# 07_LMS7002M_Power.net
KiCad netlist of a schematic drawn in Altium Designer
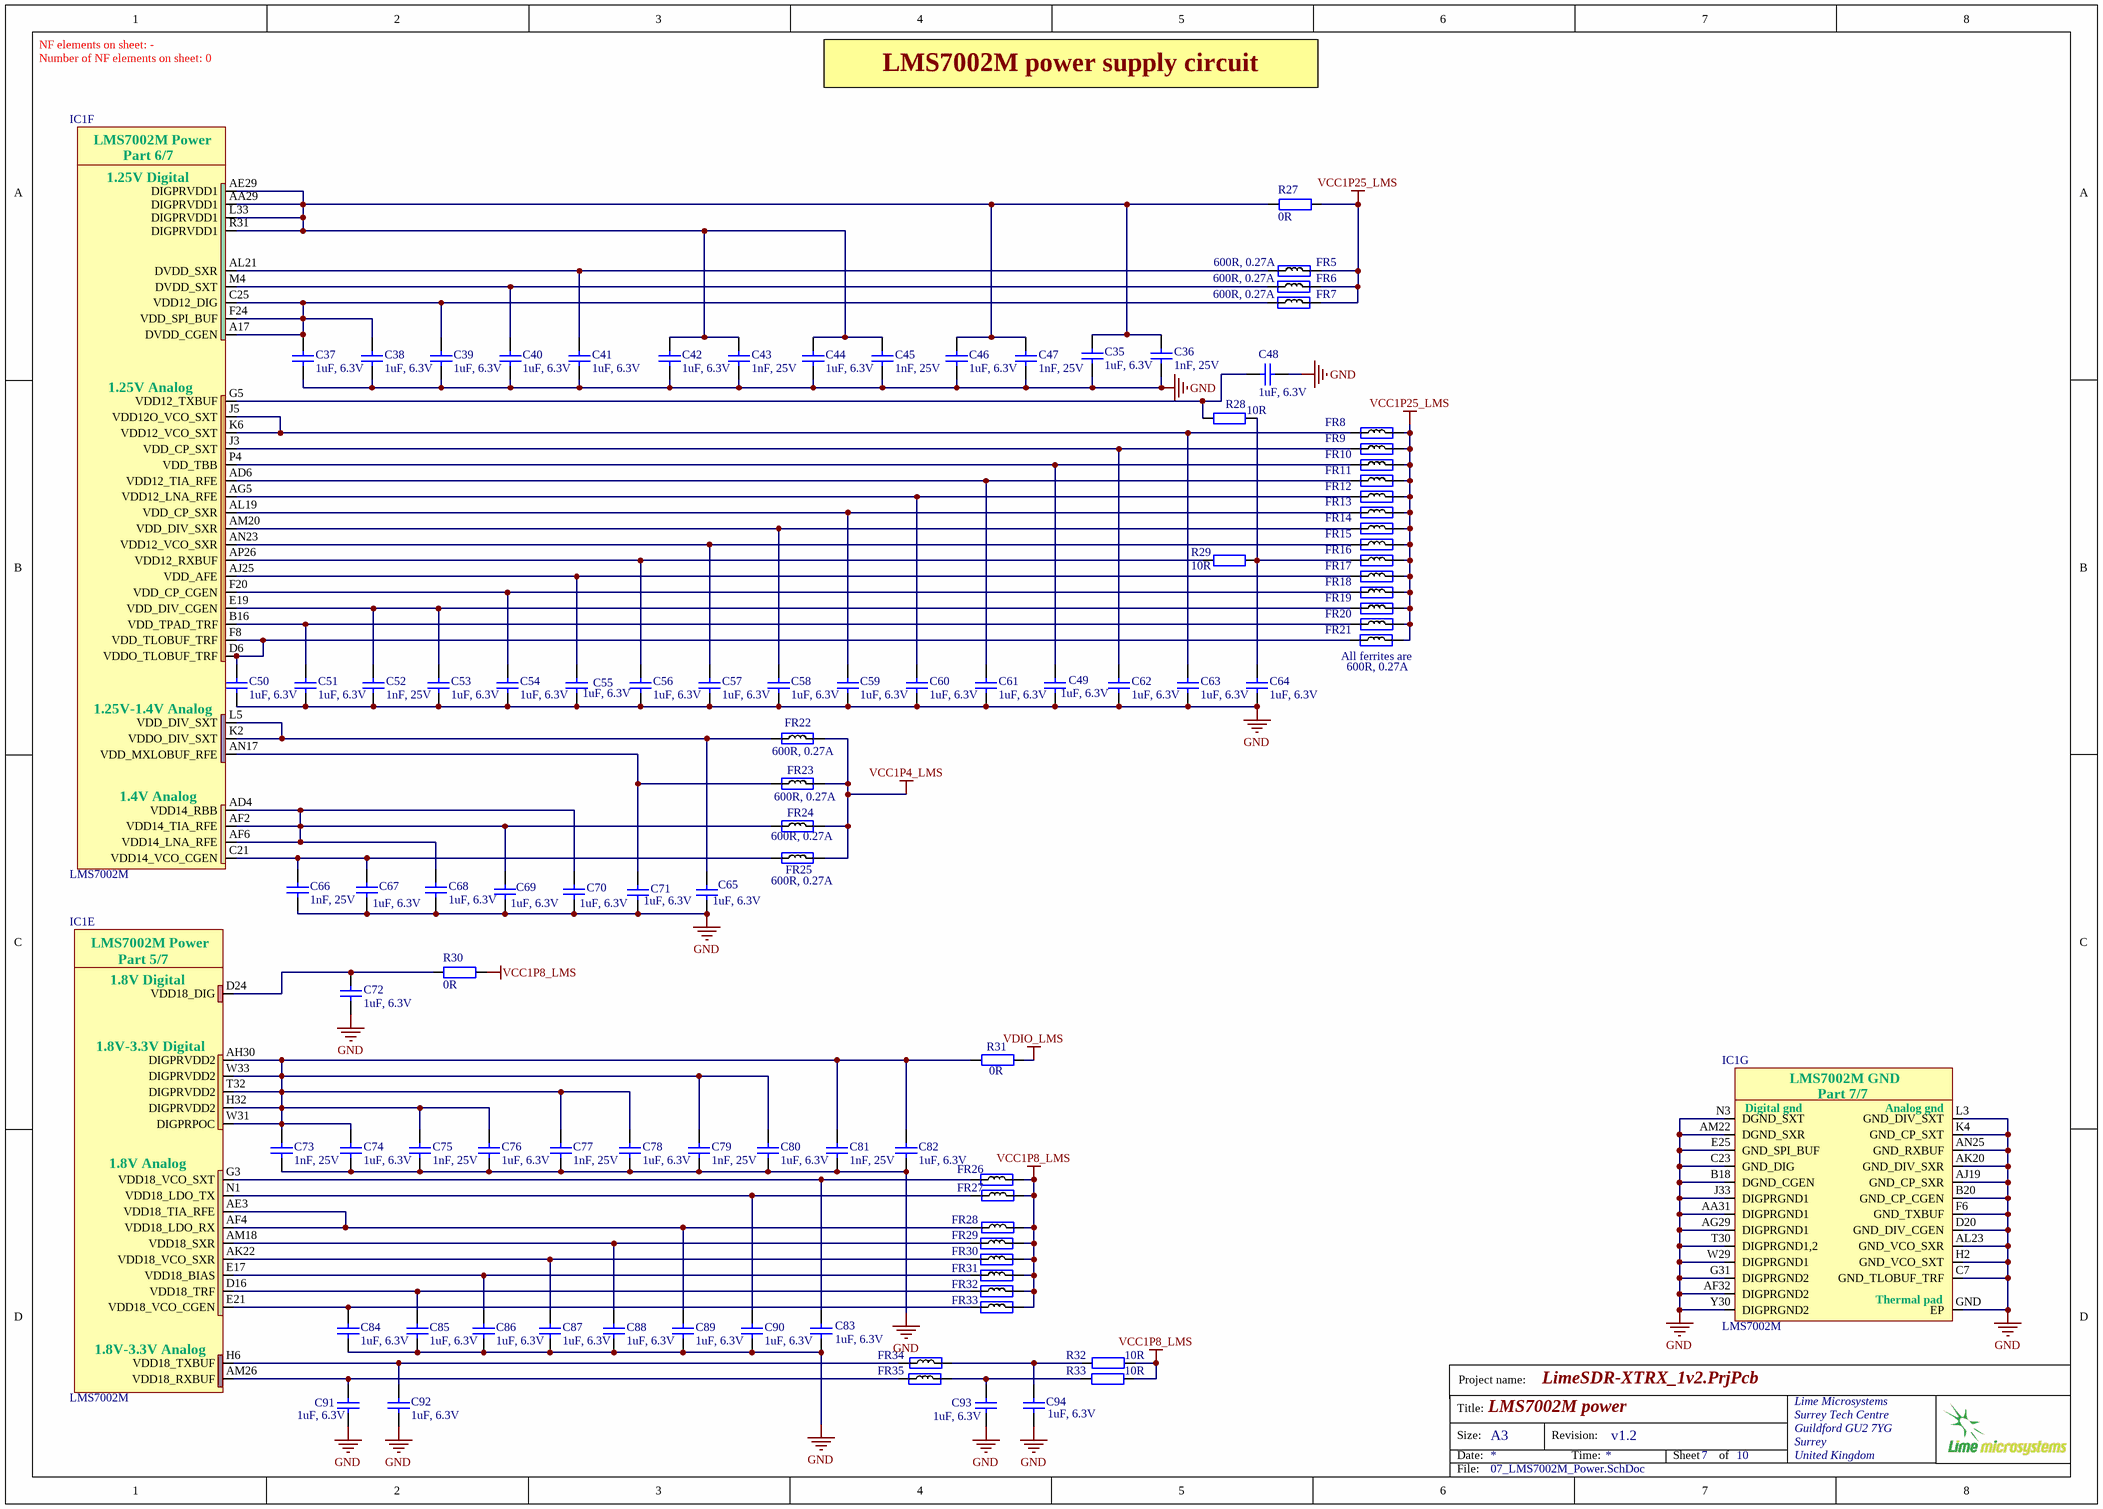
[diagram p0: 07_LMS7002M_Power.SchDoc]

(export (version "E")
  (design (tool "Eeschema 10.0.6"))
  (components
    (comp (ref "C35")
      (value "1uF, 6.3V")
      (footprint "CAP0201")
      (fields (field (name "TOLERANCE") "±20%") (field (name "MANUFACTURER") "TDK Corporation"))
      (libsource (lib "LimeMicroAltiumLib_schLib") (part "Cap_0402"))
    )
    (comp (ref "C36")
      (value "1nF, 25V")
      (footprint "CAP0201")
      (fields (field (name "TOLERANCE") "±10%") (field (name "MANUFACTURER") "TDK Corporation"))
      (libsource (lib "LimeMicroAltiumLib_schLib") (part "Cap_0402"))
    )
    (comp (ref "C37")
      (value "1uF, 6.3V")
      (footprint "CAP0201")
      (fields (field (name "TOLERANCE") "±20%") (field (name "MANUFACTURER") "TDK Corporation"))
      (libsource (lib "LimeMicroAltiumLib_schLib") (part "Cap_0402"))
    )
    (comp (ref "C38")
      (value "1uF, 6.3V")
      (footprint "CAP0201")
      (fields (field (name "TOLERANCE") "±20%") (field (name "MANUFACTURER") "TDK Corporation"))
      (libsource (lib "LimeMicroAltiumLib_schLib") (part "Cap_0402"))
    )
    (comp (ref "C39")
      (value "1uF, 6.3V")
      (footprint "CAP0201")
      (fields (field (name "TOLERANCE") "±20%") (field (name "MANUFACTURER") "TDK Corporation"))
      (libsource (lib "LimeMicroAltiumLib_schLib") (part "Cap_0402"))
    )
    (comp (ref "C40")
      (value "1uF, 6.3V")
      (footprint "CAP0201")
      (fields (field (name "TOLERANCE") "±20%") (field (name "MANUFACTURER") "TDK Corporation"))
      (libsource (lib "LimeMicroAltiumLib_schLib") (part "Cap_0402"))
    )
    (comp (ref "C41")
      (value "1uF, 6.3V")
      (footprint "CAP0201")
      (fields (field (name "TOLERANCE") "±20%") (field (name "MANUFACTURER") "TDK Corporation"))
      (libsource (lib "LimeMicroAltiumLib_schLib") (part "Cap_0402"))
    )
    (comp (ref "C42")
      (value "1uF, 6.3V")
      (footprint "CAP0201")
      (fields (field (name "TOLERANCE") "±20%") (field (name "MANUFACTURER") "TDK Corporation"))
      (libsource (lib "LimeMicroAltiumLib_schLib") (part "Cap_0402"))
    )
    (comp (ref "C43")
      (value "1nF, 25V")
      (footprint "CAP0201")
      (fields (field (name "TOLERANCE") "±10%") (field (name "MANUFACTURER") "TDK Corporation"))
      (libsource (lib "LimeMicroAltiumLib_schLib") (part "Cap_0402"))
    )
    (comp (ref "C44")
      (value "1uF, 6.3V")
      (footprint "CAP0201")
      (fields (field (name "TOLERANCE") "±20%") (field (name "MANUFACTURER") "TDK Corporation"))
      (libsource (lib "LimeMicroAltiumLib_schLib") (part "Cap_0402"))
    )
    (comp (ref "C45")
      (value "1nF, 25V")
      (footprint "CAP0201")
      (fields (field (name "TOLERANCE") "±10%") (field (name "MANUFACTURER") "TDK Corporation"))
      (libsource (lib "LimeMicroAltiumLib_schLib") (part "Cap_0402"))
    )
    (comp (ref "C46")
      (value "1uF, 6.3V")
      (footprint "CAP0201")
      (fields (field (name "TOLERANCE") "±20%") (field (name "MANUFACTURER") "TDK Corporation"))
      (libsource (lib "LimeMicroAltiumLib_schLib") (part "Cap_0402"))
    )
    (comp (ref "C47")
      (value "1nF, 25V")
      (footprint "CAP0201")
      (fields (field (name "TOLERANCE") "±10%") (field (name "MANUFACTURER") "TDK Corporation"))
      (libsource (lib "LimeMicroAltiumLib_schLib") (part "Cap_0402"))
    )
    (comp (ref "C48")
      (value "1uF, 6.3V")
      (footprint "CAP0201")
      (fields (field (name "TOLERANCE") "±20%") (field (name "MANUFACTURER") "TDK Corporation"))
      (libsource (lib "LimeMicroAltiumLib_schLib") (part "Cap_0402"))
    )
    (comp (ref "C49")
      (value "1uF, 6.3V")
      (footprint "CAP0201")
      (fields (field (name "TOLERANCE") "±20%") (field (name "MANUFACTURER") "TDK Corporation"))
      (libsource (lib "LimeMicroAltiumLib_schLib") (part "Cap_0402"))
    )
    (comp (ref "C50")
      (value "1uF, 6.3V")
      (footprint "CAP0201")
      (fields (field (name "TOLERANCE") "±20%") (field (name "MANUFACTURER") "TDK Corporation"))
      (libsource (lib "LimeMicroAltiumLib_schLib") (part "Cap_0402"))
    )
    (comp (ref "C51")
      (value "1uF, 6.3V")
      (footprint "CAP0201")
      (fields (field (name "TOLERANCE") "±20%") (field (name "MANUFACTURER") "TDK Corporation"))
      (libsource (lib "LimeMicroAltiumLib_schLib") (part "Cap_0402"))
    )
    (comp (ref "C52")
      (value "1nF, 25V")
      (footprint "CAP0201")
      (fields (field (name "TOLERANCE") "±10%") (field (name "MANUFACTURER") "TDK Corporation"))
      (libsource (lib "LimeMicroAltiumLib_schLib") (part "Cap_0402"))
    )
    (comp (ref "C53")
      (value "1uF, 6.3V")
      (footprint "CAP0201")
      (fields (field (name "TOLERANCE") "±20%") (field (name "MANUFACTURER") "TDK Corporation"))
      (libsource (lib "LimeMicroAltiumLib_schLib") (part "Cap_0402"))
    )
    (comp (ref "C54")
      (value "1uF, 6.3V")
      (footprint "CAP0201")
      (fields (field (name "TOLERANCE") "±20%") (field (name "MANUFACTURER") "TDK Corporation"))
      (libsource (lib "LimeMicroAltiumLib_schLib") (part "Cap_0402"))
    )
    (comp (ref "C55")
      (value "1uF, 6.3V")
      (footprint "CAP0201")
      (fields (field (name "TOLERANCE") "±20%") (field (name "MANUFACTURER") "TDK Corporation"))
      (libsource (lib "LimeMicroAltiumLib_schLib") (part "Cap_0402"))
    )
    (comp (ref "C56")
      (value "1uF, 6.3V")
      (footprint "CAP0201")
      (fields (field (name "TOLERANCE") "±20%") (field (name "MANUFACTURER") "TDK Corporation"))
      (libsource (lib "LimeMicroAltiumLib_schLib") (part "Cap_0402"))
    )
    (comp (ref "C57")
      (value "1uF, 6.3V")
      (footprint "CAP0201")
      (fields (field (name "TOLERANCE") "±20%") (field (name "MANUFACTURER") "TDK Corporation"))
      (libsource (lib "LimeMicroAltiumLib_schLib") (part "Cap_0402"))
    )
    (comp (ref "C58")
      (value "1uF, 6.3V")
      (footprint "CAP0201")
      (fields (field (name "TOLERANCE") "±20%") (field (name "MANUFACTURER") "TDK Corporation"))
      (libsource (lib "LimeMicroAltiumLib_schLib") (part "Cap_0402"))
    )
    (comp (ref "C59")
      (value "1uF, 6.3V")
      (footprint "CAP0201")
      (fields (field (name "TOLERANCE") "±20%") (field (name "MANUFACTURER") "TDK Corporation"))
      (libsource (lib "LimeMicroAltiumLib_schLib") (part "Cap_0402"))
    )
    (comp (ref "C60")
      (value "1uF, 6.3V")
      (footprint "CAP0201")
      (fields (field (name "TOLERANCE") "±20%") (field (name "MANUFACTURER") "TDK Corporation"))
      (libsource (lib "LimeMicroAltiumLib_schLib") (part "Cap_0402"))
    )
    (comp (ref "C61")
      (value "1uF, 6.3V")
      (footprint "CAP0201")
      (fields (field (name "TOLERANCE") "±20%") (field (name "MANUFACTURER") "TDK Corporation"))
      (libsource (lib "LimeMicroAltiumLib_schLib") (part "Cap_0402"))
    )
    (comp (ref "C62")
      (value "1uF, 6.3V")
      (footprint "CAP0201")
      (fields (field (name "TOLERANCE") "±20%") (field (name "MANUFACTURER") "TDK Corporation"))
      (libsource (lib "LimeMicroAltiumLib_schLib") (part "Cap_0402"))
    )
    (comp (ref "C63")
      (value "1uF, 6.3V")
      (footprint "CAP0201")
      (fields (field (name "TOLERANCE") "±20%") (field (name "MANUFACTURER") "TDK Corporation"))
      (libsource (lib "LimeMicroAltiumLib_schLib") (part "Cap_0402"))
    )
    (comp (ref "C64")
      (value "1uF, 6.3V")
      (footprint "CAP0201")
      (fields (field (name "TOLERANCE") "±20%") (field (name "MANUFACTURER") "TDK Corporation"))
      (libsource (lib "LimeMicroAltiumLib_schLib") (part "Cap_0402"))
    )
    (comp (ref "C65")
      (value "1uF, 6.3V")
      (footprint "CAP0201")
      (fields (field (name "TOLERANCE") "±20%") (field (name "MANUFACTURER") "TDK Corporation"))
      (libsource (lib "LimeMicroAltiumLib_schLib") (part "Cap_0402"))
    )
    (comp (ref "C66")
      (value "1nF, 25V")
      (footprint "CAP0201")
      (fields (field (name "TOLERANCE") "±10%") (field (name "MANUFACTURER") "TDK Corporation"))
      (libsource (lib "LimeMicroAltiumLib_schLib") (part "Cap_0402"))
    )
    (comp (ref "C67")
      (value "1uF, 6.3V")
      (footprint "CAP0201")
      (fields (field (name "TOLERANCE") "±20%") (field (name "MANUFACTURER") "TDK Corporation"))
      (libsource (lib "LimeMicroAltiumLib_schLib") (part "Cap_0402"))
    )
    (comp (ref "C68")
      (value "1uF, 6.3V")
      (footprint "CAP0201")
      (fields (field (name "TOLERANCE") "±20%") (field (name "MANUFACTURER") "TDK Corporation"))
      (libsource (lib "LimeMicroAltiumLib_schLib") (part "Cap_0402"))
    )
    (comp (ref "C69")
      (value "1uF, 6.3V")
      (footprint "CAP0201")
      (fields (field (name "TOLERANCE") "±20%") (field (name "MANUFACTURER") "TDK Corporation"))
      (libsource (lib "LimeMicroAltiumLib_schLib") (part "Cap_0402"))
    )
    (comp (ref "C70")
      (value "1uF, 6.3V")
      (footprint "CAP0201")
      (fields (field (name "TOLERANCE") "±20%") (field (name "MANUFACTURER") "TDK Corporation"))
      (libsource (lib "LimeMicroAltiumLib_schLib") (part "Cap_0402"))
    )
    (comp (ref "C71")
      (value "1uF, 6.3V")
      (footprint "CAP0201")
      (fields (field (name "TOLERANCE") "±20%") (field (name "MANUFACTURER") "TDK Corporation"))
      (libsource (lib "LimeMicroAltiumLib_schLib") (part "Cap_0402"))
    )
    (comp (ref "C72")
      (value "1uF, 6.3V")
      (footprint "CAP0201")
      (fields (field (name "TOLERANCE") "±20%") (field (name "MANUFACTURER") "TDK Corporation"))
      (libsource (lib "LimeMicroAltiumLib_schLib") (part "Cap_0402"))
    )
    (comp (ref "C73")
      (value "1nF, 25V")
      (footprint "CAP0201")
      (fields (field (name "TOLERANCE") "±10%") (field (name "MANUFACTURER") "TDK Corporation"))
      (libsource (lib "LimeMicroAltiumLib_schLib") (part "Cap_0402"))
    )
    (comp (ref "C74")
      (value "1uF, 6.3V")
      (footprint "CAP0201")
      (fields (field (name "TOLERANCE") "±20%") (field (name "MANUFACTURER") "TDK Corporation"))
      (libsource (lib "LimeMicroAltiumLib_schLib") (part "Cap_0402"))
    )
    (comp (ref "C75")
      (value "1nF, 25V")
      (footprint "CAP0201")
      (fields (field (name "TOLERANCE") "±10%") (field (name "MANUFACTURER") "TDK Corporation"))
      (libsource (lib "LimeMicroAltiumLib_schLib") (part "Cap_0402"))
    )
    (comp (ref "C76")
      (value "1uF, 6.3V")
      (footprint "CAP0201")
      (fields (field (name "TOLERANCE") "±20%") (field (name "MANUFACTURER") "TDK Corporation"))
      (libsource (lib "LimeMicroAltiumLib_schLib") (part "Cap_0402"))
    )
    (comp (ref "C77")
      (value "1nF, 25V")
      (footprint "CAP0201")
      (fields (field (name "TOLERANCE") "±10%") (field (name "MANUFACTURER") "TDK Corporation"))
      (libsource (lib "LimeMicroAltiumLib_schLib") (part "Cap_0402"))
    )
    (comp (ref "C78")
      (value "1uF, 6.3V")
      (footprint "CAP0201")
      (fields (field (name "TOLERANCE") "±20%") (field (name "MANUFACTURER") "TDK Corporation"))
      (libsource (lib "LimeMicroAltiumLib_schLib") (part "Cap_0402"))
    )
    (comp (ref "C79")
      (value "1nF, 25V")
      (footprint "CAP0201")
      (fields (field (name "TOLERANCE") "±10%") (field (name "MANUFACTURER") "TDK Corporation"))
      (libsource (lib "LimeMicroAltiumLib_schLib") (part "Cap_0402"))
    )
    (comp (ref "C80")
      (value "1uF, 6.3V")
      (footprint "CAP0201")
      (fields (field (name "TOLERANCE") "±20%") (field (name "MANUFACTURER") "TDK Corporation"))
      (libsource (lib "LimeMicroAltiumLib_schLib") (part "Cap_0402"))
    )
    (comp (ref "C81")
      (value "1nF, 25V")
      (footprint "CAP0201")
      (fields (field (name "TOLERANCE") "±10%") (field (name "MANUFACTURER") "TDK Corporation"))
      (libsource (lib "LimeMicroAltiumLib_schLib") (part "Cap_0402"))
    )
    (comp (ref "C82")
      (value "1uF, 6.3V")
      (footprint "CAP0201")
      (fields (field (name "TOLERANCE") "±20%") (field (name "MANUFACTURER") "TDK Corporation"))
      (libsource (lib "LimeMicroAltiumLib_schLib") (part "Cap_0402"))
    )
    (comp (ref "C83")
      (value "1uF, 6.3V")
      (footprint "CAP0201")
      (fields (field (name "TOLERANCE") "±20%") (field (name "MANUFACTURER") "TDK Corporation"))
      (libsource (lib "LimeMicroAltiumLib_schLib") (part "Cap_0402"))
    )
    (comp (ref "C84")
      (value "1uF, 6.3V")
      (footprint "CAP0201")
      (fields (field (name "TOLERANCE") "±20%") (field (name "MANUFACTURER") "TDK Corporation"))
      (libsource (lib "LimeMicroAltiumLib_schLib") (part "Cap_0402"))
    )
    (comp (ref "C85")
      (value "1uF, 6.3V")
      (footprint "CAP0201")
      (fields (field (name "TOLERANCE") "±20%") (field (name "MANUFACTURER") "TDK Corporation"))
      (libsource (lib "LimeMicroAltiumLib_schLib") (part "Cap_0402"))
    )
    (comp (ref "C86")
      (value "1uF, 6.3V")
      (footprint "CAP0201")
      (fields (field (name "TOLERANCE") "±20%") (field (name "MANUFACTURER") "TDK Corporation"))
      (libsource (lib "LimeMicroAltiumLib_schLib") (part "Cap_0402"))
    )
    (comp (ref "C87")
      (value "1uF, 6.3V")
      (footprint "CAP0201")
      (fields (field (name "TOLERANCE") "±20%") (field (name "MANUFACTURER") "TDK Corporation"))
      (libsource (lib "LimeMicroAltiumLib_schLib") (part "Cap_0402"))
    )
    (comp (ref "C88")
      (value "1uF, 6.3V")
      (footprint "CAP0201")
      (fields (field (name "TOLERANCE") "±20%") (field (name "MANUFACTURER") "TDK Corporation"))
      (libsource (lib "LimeMicroAltiumLib_schLib") (part "Cap_0402"))
    )
    (comp (ref "C89")
      (value "1uF, 6.3V")
      (footprint "CAP0201")
      (fields (field (name "TOLERANCE") "±20%") (field (name "MANUFACTURER") "TDK Corporation"))
      (libsource (lib "LimeMicroAltiumLib_schLib") (part "Cap_0402"))
    )
    (comp (ref "C90")
      (value "1uF, 6.3V")
      (footprint "CAP0201")
      (fields (field (name "TOLERANCE") "±20%") (field (name "MANUFACTURER") "TDK Corporation"))
      (libsource (lib "LimeMicroAltiumLib_schLib") (part "Cap_0402"))
    )
    (comp (ref "C91")
      (value "1uF, 6.3V")
      (footprint "CAP0201")
      (fields (field (name "TOLERANCE") "±20%") (field (name "MANUFACTURER") "TDK Corporation"))
      (libsource (lib "LimeMicroAltiumLib_schLib") (part "Cap_0402"))
    )
    (comp (ref "C92")
      (value "1uF, 6.3V")
      (footprint "CAP0201")
      (fields (field (name "TOLERANCE") "±20%") (field (name "MANUFACTURER") "TDK Corporation"))
      (libsource (lib "LimeMicroAltiumLib_schLib") (part "Cap_0402"))
    )
    (comp (ref "C93")
      (value "1uF, 6.3V")
      (footprint "CAP0201")
      (fields (field (name "TOLERANCE") "±20%") (field (name "MANUFACTURER") "TDK Corporation"))
      (libsource (lib "LimeMicroAltiumLib_schLib") (part "Cap_0402"))
    )
    (comp (ref "C94")
      (value "1uF, 6.3V")
      (footprint "CAP0201")
      (fields (field (name "TOLERANCE") "±20%") (field (name "MANUFACTURER") "TDK Corporation"))
      (libsource (lib "LimeMicroAltiumLib_schLib") (part "Cap_0402"))
    )
    (comp (ref "FR5")
      (value "600R, 0.27A")
      (footprint "RES0201")
      (fields (field (name "MANUFACTURER") "Taiyo Yuden"))
      (libsource (lib "LimeMicroAltiumLib_schLib") (part "Ferrite"))
    )
    (comp (ref "FR6")
      (value "600R, 0.27A")
      (footprint "RES0201")
      (fields (field (name "MANUFACTURER") "Taiyo Yuden"))
      (libsource (lib "LimeMicroAltiumLib_schLib") (part "Ferrite"))
    )
    (comp (ref "FR7")
      (value "600R, 0.27A")
      (footprint "RES0201")
      (fields (field (name "MANUFACTURER") "Taiyo Yuden"))
      (libsource (lib "LimeMicroAltiumLib_schLib") (part "Ferrite"))
    )
    (comp (ref "FR8")
      (value "600R, 0.27A")
      (footprint "RES0201")
      (fields (field (name "MANUFACTURER") "Taiyo Yuden"))
      (libsource (lib "LimeMicroAltiumLib_schLib") (part "Ferrite"))
    )
    (comp (ref "FR9")
      (value "600R, 0.27A")
      (footprint "RES0201")
      (fields (field (name "MANUFACTURER") "Taiyo Yuden"))
      (libsource (lib "LimeMicroAltiumLib_schLib") (part "Ferrite"))
    )
    (comp (ref "FR10")
      (value "600R, 0.27A")
      (footprint "RES0201")
      (fields (field (name "MANUFACTURER") "Taiyo Yuden"))
      (libsource (lib "LimeMicroAltiumLib_schLib") (part "Ferrite"))
    )
    (comp (ref "FR11")
      (value "600R, 0.27A")
      (footprint "RES0201")
      (fields (field (name "MANUFACTURER") "Taiyo Yuden"))
      (libsource (lib "LimeMicroAltiumLib_schLib") (part "Ferrite"))
    )
    (comp (ref "FR12")
      (value "600R, 0.27A")
      (footprint "RES0201")
      (fields (field (name "MANUFACTURER") "Taiyo Yuden"))
      (libsource (lib "LimeMicroAltiumLib_schLib") (part "Ferrite"))
    )
    (comp (ref "FR13")
      (value "600R, 0.27A")
      (footprint "RES0201")
      (fields (field (name "MANUFACTURER") "Taiyo Yuden"))
      (libsource (lib "LimeMicroAltiumLib_schLib") (part "Ferrite"))
    )
    (comp (ref "FR14")
      (value "600R, 0.27A")
      (footprint "RES0201")
      (fields (field (name "MANUFACTURER") "Taiyo Yuden"))
      (libsource (lib "LimeMicroAltiumLib_schLib") (part "Ferrite"))
    )
    (comp (ref "FR15")
      (value "600R, 0.27A")
      (footprint "RES0201")
      (fields (field (name "MANUFACTURER") "Taiyo Yuden"))
      (libsource (lib "LimeMicroAltiumLib_schLib") (part "Ferrite"))
    )
    (comp (ref "FR16")
      (value "600R, 0.27A")
      (footprint "RES0201")
      (fields (field (name "MANUFACTURER") "Taiyo Yuden"))
      (libsource (lib "LimeMicroAltiumLib_schLib") (part "Ferrite"))
    )
    (comp (ref "FR17")
      (value "600R, 0.27A")
      (footprint "RES0201")
      (fields (field (name "MANUFACTURER") "Taiyo Yuden"))
      (libsource (lib "LimeMicroAltiumLib_schLib") (part "Ferrite"))
    )
    (comp (ref "FR18")
      (value "600R, 0.27A")
      (footprint "RES0201")
      (fields (field (name "MANUFACTURER") "Taiyo Yuden"))
      (libsource (lib "LimeMicroAltiumLib_schLib") (part "Ferrite"))
    )
    (comp (ref "FR19")
      (value "600R, 0.27A")
      (footprint "RES0201")
      (fields (field (name "MANUFACTURER") "Taiyo Yuden"))
      (libsource (lib "LimeMicroAltiumLib_schLib") (part "Ferrite"))
    )
    (comp (ref "FR20")
      (value "600R, 0.27A")
      (footprint "RES0201")
      (fields (field (name "MANUFACTURER") "Taiyo Yuden"))
      (libsource (lib "LimeMicroAltiumLib_schLib") (part "Ferrite"))
    )
    (comp (ref "FR21")
      (value "600R, 0.27A")
      (footprint "RES0201")
      (fields (field (name "MANUFACTURER") "Taiyo Yuden"))
      (libsource (lib "LimeMicroAltiumLib_schLib") (part "Ferrite"))
    )
    (comp (ref "FR22")
      (value "600R, 0.27A")
      (footprint "RES0201")
      (fields (field (name "MANUFACTURER") "Taiyo Yuden"))
      (libsource (lib "LimeMicroAltiumLib_schLib") (part "Ferrite"))
    )
    (comp (ref "FR23")
      (value "600R, 0.27A")
      (footprint "RES0201")
      (fields (field (name "MANUFACTURER") "Taiyo Yuden"))
      (libsource (lib "LimeMicroAltiumLib_schLib") (part "Ferrite"))
    )
    (comp (ref "FR24")
      (value "600R, 0.27A")
      (footprint "RES0201")
      (fields (field (name "MANUFACTURER") "Taiyo Yuden"))
      (libsource (lib "LimeMicroAltiumLib_schLib") (part "Ferrite"))
    )
    (comp (ref "FR25")
      (value "600R, 0.27A")
      (footprint "RES0201")
      (fields (field (name "MANUFACTURER") "Taiyo Yuden"))
      (libsource (lib "LimeMicroAltiumLib_schLib") (part "Ferrite"))
    )
    (comp (ref "FR26")
      (value "600R, 0.27A")
      (footprint "RES0201")
      (fields (field (name "MANUFACTURER") "Taiyo Yuden"))
      (libsource (lib "LimeMicroAltiumLib_schLib") (part "Ferrite"))
    )
    (comp (ref "FR27")
      (value "600R, 0.27A")
      (footprint "RES0201")
      (fields (field (name "MANUFACTURER") "Taiyo Yuden"))
      (libsource (lib "") (part "Ferrite_1"))
    )
    (comp (ref "FR28")
      (value "600R, 0.27A")
      (footprint "RES0201")
      (fields (field (name "MANUFACTURER") "Taiyo Yuden"))
      (libsource (lib "") (part "Ferrite_1"))
    )
    (comp (ref "FR29")
      (value "600R, 0.27A")
      (footprint "RES0201")
      (fields (field (name "MANUFACTURER") "Taiyo Yuden"))
      (libsource (lib "LimeMicroAltiumLib_schLib") (part "Ferrite"))
    )
    (comp (ref "FR30")
      (value "600R, 0.27A")
      (footprint "RES0201")
      (fields (field (name "MANUFACTURER") "Taiyo Yuden"))
      (libsource (lib "LimeMicroAltiumLib_schLib") (part "Ferrite"))
    )
    (comp (ref "FR31")
      (value "600R, 0.27A")
      (footprint "RES0201")
      (fields (field (name "MANUFACTURER") "Taiyo Yuden"))
      (libsource (lib "LimeMicroAltiumLib_schLib") (part "Ferrite"))
    )
    (comp (ref "FR32")
      (value "600R, 0.27A")
      (footprint "RES0201")
      (fields (field (name "MANUFACTURER") "Taiyo Yuden"))
      (libsource (lib "LimeMicroAltiumLib_schLib") (part "Ferrite"))
    )
    (comp (ref "FR33")
      (value "600R, 0.27A")
      (footprint "RES0201")
      (fields (field (name "MANUFACTURER") "Taiyo Yuden"))
      (libsource (lib "LimeMicroAltiumLib_schLib") (part "Ferrite"))
    )
    (comp (ref "FR34")
      (value "600R, 0.27A")
      (footprint "RES0201")
      (fields (field (name "MANUFACTURER") "Taiyo Yuden"))
      (libsource (lib "") (part "Ferrite_1"))
    )
    (comp (ref "FR35")
      (value "600R, 0.27A")
      (footprint "RES0201")
      (fields (field (name "MANUFACTURER") "Taiyo Yuden"))
      (libsource (lib "LimeMicroAltiumLib_schLib") (part "Ferrite"))
    )
    (comp (ref "IC1")
      (value "LMS7002M")
      (footprint "LMS7002M_v5_LESS_SILK")
      (description "Schematic symbol revision 4. Default footprint - 0.31mm pad")
      (fields (field (name "MANUFACTURER") "Lime Microsystems"))
      (libsource (lib "LimeMicroAltiumLib_schLib_r04") (part "LMS7002Mr4"))
    )
    (comp (ref "R27")
      (value "0R")
      (footprint "RES0402")
      (fields (field (name "MANUFACTURER") "Yageo") (field (name "TOLERANCE") "Jumper"))
      (libsource (lib "LimeMicroAltiumLib_schLib") (part "Res_0402"))
    )
    (comp (ref "R28")
      (value "10R")
      (footprint "RES0201")
      (fields
        (field (name "MANUFACTURER") "Panasonic Electronic Components")
        (field (name "TOLERANCE") "±1%")
      )
      (libsource (lib "LimeMicroAltiumLib_schLib") (part "Res_0402"))
    )
    (comp (ref "R29")
      (value "10R")
      (footprint "RES0201")
      (fields
        (field (name "MANUFACTURER") "Panasonic Electronic Components")
        (field (name "TOLERANCE") "±1%")
      )
      (libsource (lib "LimeMicroAltiumLib_schLib") (part "Res_0402"))
    )
    (comp (ref "R30")
      (value "0R")
      (footprint "RES0201")
      (fields (field (name "MANUFACTURER") "Yageo") (field (name "TOLERANCE") "5%"))
      (libsource (lib "LimeMicroAltiumLib_schLib") (part "Res_0402"))
    )
    (comp (ref "R31")
      (value "0R")
      (footprint "RES0402")
      (fields (field (name "MANUFACTURER") "Yageo") (field (name "TOLERANCE") "Jumper"))
      (libsource (lib "LimeMicroAltiumLib_schLib") (part "Res_0402"))
    )
    (comp (ref "R32")
      (value "10R")
      (footprint "RES0201")
      (fields
        (field (name "MANUFACTURER") "Panasonic Electronic Components")
        (field (name "TOLERANCE") "±1%")
      )
      (libsource (lib "LimeMicroAltiumLib_schLib") (part "Res_0402"))
    )
    (comp (ref "R33")
      (value "10R")
      (footprint "RES0201")
      (fields
        (field (name "MANUFACTURER") "Panasonic Electronic Components")
        (field (name "TOLERANCE") "±1%")
      )
      (libsource (lib "LimeMicroAltiumLib_schLib") (part "Res_0402"))
    )
  )
  (nets
    (net (code "1") (name "GND") (class "Default")
      (node (ref "C35") (pin "2") (pinfunction "2_2") (pintype "passive"))
      (node (ref "C36") (pin "2") (pinfunction "2_2") (pintype "passive"))
      (node (ref "C37") (pin "2") (pinfunction "2_2") (pintype "passive"))
      (node (ref "C38") (pin "2") (pinfunction "2_2") (pintype "passive"))
      (node (ref "C39") (pin "2") (pinfunction "2_2") (pintype "passive"))
      (node (ref "C40") (pin "1") (pinfunction "1_1") (pintype "passive"))
      (node (ref "C41") (pin "2") (pinfunction "2_2") (pintype "passive"))
      (node (ref "C42") (pin "2") (pinfunction "2_2") (pintype "passive"))
      (node (ref "C43") (pin "2") (pinfunction "2_2") (pintype "passive"))
      (node (ref "C44") (pin "2") (pinfunction "2_2") (pintype "passive"))
      (node (ref "C45") (pin "2") (pinfunction "2_2") (pintype "passive"))
      (node (ref "C46") (pin "2") (pinfunction "2_2") (pintype "passive"))
      (node (ref "C47") (pin "2") (pinfunction "2_2") (pintype "passive"))
      (node (ref "C48") (pin "2") (pinfunction "2_2") (pintype "passive"))
      (node (ref "C49") (pin "2") (pinfunction "2_2") (pintype "passive"))
      (node (ref "C50") (pin "2") (pinfunction "2_2") (pintype "passive"))
      (node (ref "C51") (pin "2") (pinfunction "2_2") (pintype "passive"))
      (node (ref "C52") (pin "2") (pinfunction "2_2") (pintype "passive"))
      (node (ref "C53") (pin "2") (pinfunction "2_2") (pintype "passive"))
      (node (ref "C54") (pin "1") (pinfunction "1_1") (pintype "passive"))
      (node (ref "C55") (pin "2") (pinfunction "2_2") (pintype "passive"))
      (node (ref "C56") (pin "2") (pinfunction "2_2") (pintype "passive"))
      (node (ref "C57") (pin "2") (pinfunction "2_2") (pintype "passive"))
      (node (ref "C58") (pin "2") (pinfunction "2_2") (pintype "passive"))
      (node (ref "C59") (pin "2") (pinfunction "2_2") (pintype "passive"))
      (node (ref "C60") (pin "2") (pinfunction "2_2") (pintype "passive"))
      (node (ref "C61") (pin "1") (pinfunction "1_1") (pintype "passive"))
      (node (ref "C62") (pin "2") (pinfunction "2_2") (pintype "passive"))
      (node (ref "C63") (pin "1") (pinfunction "1_1") (pintype "passive"))
      (node (ref "C64") (pin "1") (pinfunction "1_1") (pintype "passive"))
      (node (ref "C65") (pin "2") (pinfunction "2_2") (pintype "passive"))
      (node (ref "C66") (pin "2") (pinfunction "2_2") (pintype "passive"))
      (node (ref "C67") (pin "2") (pinfunction "2_2") (pintype "passive"))
      (node (ref "C68") (pin "2") (pinfunction "2_2") (pintype "passive"))
      (node (ref "C69") (pin "2") (pinfunction "2_2") (pintype "passive"))
      (node (ref "C70") (pin "2") (pinfunction "2_2") (pintype "passive"))
      (node (ref "C71") (pin "2") (pinfunction "2_2") (pintype "passive"))
      (node (ref "C72") (pin "2") (pinfunction "2_2") (pintype "passive"))
      (node (ref "C73") (pin "2") (pinfunction "2_2") (pintype "passive"))
      (node (ref "C74") (pin "2") (pinfunction "2_2") (pintype "passive"))
      (node (ref "C75") (pin "2") (pinfunction "2_2") (pintype "passive"))
      (node (ref "C76") (pin "2") (pinfunction "2_2") (pintype "passive"))
      (node (ref "C77") (pin "2") (pinfunction "2_2") (pintype "passive"))
      (node (ref "C78") (pin "2") (pinfunction "2_2") (pintype "passive"))
      (node (ref "C79") (pin "2") (pinfunction "2_2") (pintype "passive"))
      (node (ref "C80") (pin "2") (pinfunction "2_2") (pintype "passive"))
      (node (ref "C81") (pin "2") (pinfunction "2_2") (pintype "passive"))
      (node (ref "C82") (pin "2") (pinfunction "2_2") (pintype "passive"))
      (node (ref "C83") (pin "2") (pinfunction "2_2") (pintype "passive"))
      (node (ref "C84") (pin "2") (pinfunction "2_2") (pintype "passive"))
      (node (ref "C85") (pin "2") (pinfunction "2_2") (pintype "passive"))
      (node (ref "C86") (pin "2") (pinfunction "2_2") (pintype "passive"))
      (node (ref "C87") (pin "2") (pinfunction "2_2") (pintype "passive"))
      (node (ref "C88") (pin "2") (pinfunction "2_2") (pintype "passive"))
      (node (ref "C89") (pin "2") (pinfunction "2_2") (pintype "passive"))
      (node (ref "C90") (pin "2") (pinfunction "2_2") (pintype "passive"))
      (node (ref "C91") (pin "2") (pinfunction "2_2") (pintype "passive"))
      (node (ref "C92") (pin "2") (pinfunction "2_2") (pintype "passive"))
      (node (ref "C93") (pin "2") (pinfunction "2_2") (pintype "passive"))
      (node (ref "C94") (pin "2") (pinfunction "2_2") (pintype "passive"))
      (node (ref "IC1") (pin "AA31") (pinfunction "DIGPRGND1_AA31") (pintype "passive"))
      (node (ref "IC1") (pin "AF32") (pinfunction "DIGPRGND2_AF32") (pintype "passive"))
      (node (ref "IC1") (pin "AG29") (pinfunction "DIGPRGND1_AG29") (pintype "passive"))
      (node (ref "IC1") (pin "AJ19") (pinfunction "GND_CP_SXR_AJ19") (pintype "passive"))
      (node (ref "IC1") (pin "AK20") (pinfunction "GND_DIV_SXR_AK20") (pintype "passive"))
      (node (ref "IC1") (pin "AL23") (pinfunction "GND_VCO_SXR_AL23") (pintype "passive"))
      (node (ref "IC1") (pin "AM22") (pinfunction "DGND_SXR_AM22") (pintype "passive"))
      (node (ref "IC1") (pin "AN25") (pinfunction "GND_RXBUF_AN25") (pintype "passive"))
      (node (ref "IC1") (pin "B18") (pinfunction "DGND_CGEN_B18") (pintype "passive"))
      (node (ref "IC1") (pin "B20") (pinfunction "GND_CP_CGEN_B20") (pintype "passive"))
      (node (ref "IC1") (pin "C23") (pinfunction "GND_DIG_C23") (pintype "passive"))
      (node (ref "IC1") (pin "C7") (pinfunction "GND_TLOBUF_TRF_C7") (pintype "passive"))
      (node (ref "IC1") (pin "D20") (pinfunction "GND_DIV_CGEN_D20") (pintype "passive"))
      (node (ref "IC1") (pin "E25") (pinfunction "GND_SPI_BUF_E25") (pintype "passive"))
      (node (ref "IC1") (pin "F6") (pinfunction "GND_TXBUF_F6") (pintype "passive"))
      (node (ref "IC1") (pin "G31") (pinfunction "DIGPRGND2_G31") (pintype "passive"))
      (node (ref "IC1") (pin "GND") (pinfunction "EP_GND") (pintype "passive"))
      (node (ref "IC1") (pin "H2") (pinfunction "GND_VCO_SXT_H2") (pintype "passive"))
      (node (ref "IC1") (pin "J33") (pinfunction "DIGPRGND1_J33") (pintype "passive"))
      (node (ref "IC1") (pin "K4") (pinfunction "GND_CP_SXT_K4") (pintype "passive"))
      (node (ref "IC1") (pin "L3") (pinfunction "GND_DIV_SXT_L3") (pintype "passive"))
      (node (ref "IC1") (pin "N3") (pinfunction "DGND_SXT_N3") (pintype "passive"))
      (node (ref "IC1") (pin "T30") (pinfunction "DIGPRGND1,2_T30") (pintype "passive"))
      (node (ref "IC1") (pin "W29") (pinfunction "DIGPRGND1_W29") (pintype "passive"))
      (node (ref "IC1") (pin "Y30") (pinfunction "DIGPRGND2_Y30") (pintype "passive"))
    )
    (net (code "2") (name "Net-(C35-Pad1)") (class "Default")
      (node (ref "C35") (pin "1") (pinfunction "1_1") (pintype "passive"))
      (node (ref "C36") (pin "1") (pinfunction "1_1") (pintype "passive"))
      (node (ref "C42") (pin "1") (pinfunction "1_1") (pintype "passive"))
      (node (ref "C43") (pin "1") (pinfunction "1_1") (pintype "passive"))
      (node (ref "C44") (pin "1") (pinfunction "1_1") (pintype "passive"))
      (node (ref "C45") (pin "1") (pinfunction "1_1") (pintype "passive"))
      (node (ref "C46") (pin "1") (pinfunction "1_1") (pintype "passive"))
      (node (ref "C47") (pin "1") (pinfunction "1_1") (pintype "passive"))
      (node (ref "IC1") (pin "AA29") (pinfunction "DIGPRVDD1_AA29") (pintype "power_in"))
      (node (ref "IC1") (pin "AE29") (pinfunction "DIGPRVDD1_AE29") (pintype "power_in"))
      (node (ref "IC1") (pin "L33") (pinfunction "DIGPRVDD1_L33") (pintype "power_in"))
      (node (ref "IC1") (pin "R31") (pinfunction "DIGPRVDD1_R31") (pintype "power_in"))
      (node (ref "R27") (pin "2") (pinfunction "2_2") (pintype "passive"))
    )
    (net (code "3") (name "Net-(C64-Pad2)") (class "Default")
      (node (ref "C64") (pin "2") (pinfunction "2_2") (pintype "passive"))
      (node (ref "FR16") (pin "1") (pinfunction "1_1") (pintype "passive"))
      (node (ref "R28") (pin "2") (pinfunction "2_2") (pintype "passive"))
      (node (ref "R29") (pin "2") (pinfunction "2_2") (pintype "passive"))
    )
    (net (code "4") (name "Net-(C93-Pad1)") (class "Default")
      (node (ref "C93") (pin "1") (pinfunction "1_1") (pintype "passive"))
      (node (ref "FR35") (pin "2") (pinfunction "2_2") (pintype "passive"))
      (node (ref "R33") (pin "2") (pinfunction "2_2") (pintype "passive"))
    )
    (net (code "5") (name "Net-(C94-Pad1)") (class "Default")
      (node (ref "C94") (pin "1") (pinfunction "1_1") (pintype "passive"))
      (node (ref "FR34") (pin "1") (pinfunction "1_1") (pintype "passive"))
      (node (ref "R32") (pin "1") (pinfunction "1_1") (pintype "passive"))
    )
    (net (code "6") (name "Net-(IC1E-DIGPRPOC)") (class "Default")
      (node (ref "C73") (pin "1") (pinfunction "1_1") (pintype "passive"))
      (node (ref "C74") (pin "1") (pinfunction "1_1") (pintype "passive"))
      (node (ref "C75") (pin "1") (pinfunction "1_1") (pintype "passive"))
      (node (ref "C76") (pin "1") (pinfunction "1_1") (pintype "passive"))
      (node (ref "C77") (pin "1") (pinfunction "1_1") (pintype "passive"))
      (node (ref "C78") (pin "1") (pinfunction "1_1") (pintype "passive"))
      (node (ref "C79") (pin "1") (pinfunction "1_1") (pintype "passive"))
      (node (ref "C80") (pin "1") (pinfunction "1_1") (pintype "passive"))
      (node (ref "C81") (pin "1") (pinfunction "1_1") (pintype "passive"))
      (node (ref "C82") (pin "1") (pinfunction "1_1") (pintype "passive"))
      (node (ref "IC1") (pin "AH30") (pinfunction "DIGPRVDD2_AH30") (pintype "power_in"))
      (node (ref "IC1") (pin "H32") (pinfunction "DIGPRVDD2_H32") (pintype "power_in"))
      (node (ref "IC1") (pin "T32") (pinfunction "DIGPRVDD2_T32") (pintype "power_in"))
      (node (ref "IC1") (pin "W31") (pinfunction "DIGPRPOC_W31") (pintype "power_in"))
      (node (ref "IC1") (pin "W33") (pinfunction "DIGPRVDD2_W33") (pintype "power_in"))
      (node (ref "R31") (pin "2") (pinfunction "2_2") (pintype "passive"))
    )
    (net (code "7") (name "Net-(IC1E-VDD18_BIAS)") (class "Default")
      (node (ref "C86") (pin "1") (pinfunction "1_1") (pintype "passive"))
      (node (ref "FR31") (pin "1") (pinfunction "1_1") (pintype "passive"))
      (node (ref "IC1") (pin "E17") (pinfunction "VDD18_BIAS_E17") (pintype "power_in"))
    )
    (net (code "8") (name "Net-(IC1E-VDD18_DIG)") (class "Default")
      (node (ref "C72") (pin "1") (pinfunction "1_1") (pintype "passive"))
      (node (ref "IC1") (pin "D24") (pinfunction "VDD18_DIG_D24") (pintype "power_in"))
      (node (ref "R30") (pin "1") (pinfunction "1_1") (pintype "passive"))
    )
    (net (code "9") (name "Net-(IC1E-VDD18_LDO_RX)") (class "Default")
      (node (ref "C89") (pin "1") (pinfunction "1_1") (pintype "passive"))
      (node (ref "FR28") (pin "2") (pinfunction "2_2") (pintype "passive"))
      (node (ref "IC1") (pin "AE3") (pinfunction "VDD18_TIA_RFE_AE3") (pintype "power_in"))
      (node (ref "IC1") (pin "AF4") (pinfunction "VDD18_LDO_RX_AF4") (pintype "power_in"))
    )
    (net (code "10") (name "Net-(IC1E-VDD18_LDO_TX)") (class "Default")
      (node (ref "C90") (pin "1") (pinfunction "1_1") (pintype "passive"))
      (node (ref "FR27") (pin "2") (pinfunction "2_2") (pintype "passive"))
      (node (ref "IC1") (pin "N1") (pinfunction "VDD18_LDO_TX_N1") (pintype "power_in"))
    )
    (net (code "11") (name "Net-(IC1E-VDD18_RXBUF)") (class "Default")
      (node (ref "C91") (pin "1") (pinfunction "1_1") (pintype "passive"))
      (node (ref "FR35") (pin "1") (pinfunction "1_1") (pintype "passive"))
      (node (ref "IC1") (pin "AM26") (pinfunction "VDD18_RXBUF_AM26") (pintype "power_in"))
    )
    (net (code "12") (name "Net-(IC1E-VDD18_SXR)") (class "Default")
      (node (ref "C88") (pin "1") (pinfunction "1_1") (pintype "passive"))
      (node (ref "FR29") (pin "1") (pinfunction "1_1") (pintype "passive"))
      (node (ref "IC1") (pin "AM18") (pinfunction "VDD18_SXR_AM18") (pintype "power_in"))
    )
    (net (code "13") (name "Net-(IC1E-VDD18_TRF)") (class "Default")
      (node (ref "C85") (pin "1") (pinfunction "1_1") (pintype "passive"))
      (node (ref "FR32") (pin "1") (pinfunction "1_1") (pintype "passive"))
      (node (ref "IC1") (pin "D16") (pinfunction "VDD18_TRF_D16") (pintype "power_in"))
    )
    (net (code "14") (name "Net-(IC1E-VDD18_TXBUF)") (class "Default")
      (node (ref "C92") (pin "1") (pinfunction "1_1") (pintype "passive"))
      (node (ref "FR34") (pin "2") (pinfunction "2_2") (pintype "passive"))
      (node (ref "IC1") (pin "H6") (pinfunction "VDD18_TXBUF_H6") (pintype "power_in"))
    )
    (net (code "15") (name "Net-(IC1E-VDD18_VCO_CGEN)") (class "Default")
      (node (ref "C84") (pin "1") (pinfunction "1_1") (pintype "passive"))
      (node (ref "FR33") (pin "1") (pinfunction "1_1") (pintype "passive"))
      (node (ref "IC1") (pin "E21") (pinfunction "VDD18_VCO_CGEN_E21") (pintype "power_in"))
    )
    (net (code "16") (name "Net-(IC1E-VDD18_VCO_SXR)") (class "Default")
      (node (ref "C87") (pin "1") (pinfunction "1_1") (pintype "passive"))
      (node (ref "FR30") (pin "1") (pinfunction "1_1") (pintype "passive"))
      (node (ref "IC1") (pin "AK22") (pinfunction "VDD18_VCO_SXR_AK22") (pintype "power_in"))
    )
    (net (code "17") (name "Net-(IC1E-VDD18_VCO_SXT)") (class "Default")
      (node (ref "C83") (pin "1") (pinfunction "1_1") (pintype "passive"))
      (node (ref "FR26") (pin "1") (pinfunction "1_1") (pintype "passive"))
      (node (ref "IC1") (pin "G3") (pinfunction "VDD18_VCO_SXT_G3") (pintype "power_in"))
    )
    (net (code "18") (name "Net-(IC1F-DVDD_CGEN)") (class "Default")
      (node (ref "C37") (pin "1") (pinfunction "1_1") (pintype "passive"))
      (node (ref "C38") (pin "1") (pinfunction "1_1") (pintype "passive"))
      (node (ref "C39") (pin "1") (pinfunction "1_1") (pintype "passive"))
      (node (ref "FR7") (pin "1") (pinfunction "1_1") (pintype "passive"))
      (node (ref "IC1") (pin "A17") (pinfunction "DVDD_CGEN_A17") (pintype "power_in"))
      (node (ref "IC1") (pin "C25") (pinfunction "VDD12_DIG_C25") (pintype "power_in"))
      (node (ref "IC1") (pin "F24") (pinfunction "VDD_SPI_BUF_F24") (pintype "power_in"))
    )
    (net (code "19") (name "Net-(IC1F-DVDD_SXR)") (class "Default")
      (node (ref "C41") (pin "1") (pinfunction "1_1") (pintype "passive"))
      (node (ref "FR5") (pin "1") (pinfunction "1_1") (pintype "passive"))
      (node (ref "IC1") (pin "AL21") (pinfunction "DVDD_SXR_AL21") (pintype "power_in"))
    )
    (net (code "20") (name "Net-(IC1F-DVDD_SXT)") (class "Default")
      (node (ref "C40") (pin "2") (pinfunction "2_2") (pintype "passive"))
      (node (ref "FR6") (pin "1") (pinfunction "1_1") (pintype "passive"))
      (node (ref "IC1") (pin "M4") (pinfunction "DVDD_SXT_M4") (pintype "power_in"))
    )
    (net (code "21") (name "Net-(IC1F-VDD12O_VCO_SXT)") (class "Default")
      (node (ref "C63") (pin "2") (pinfunction "2_2") (pintype "passive"))
      (node (ref "FR8") (pin "1") (pinfunction "1_1") (pintype "passive"))
      (node (ref "IC1") (pin "J5") (pinfunction "VDD12O_VCO_SXT_J5") (pintype "power_in"))
      (node (ref "IC1") (pin "K6") (pinfunction "VDD12_VCO_SXT_K6") (pintype "power_in"))
    )
    (net (code "22") (name "Net-(IC1F-VDD12_LNA_RFE)") (class "Default")
      (node (ref "C60") (pin "1") (pinfunction "1_1") (pintype "passive"))
      (node (ref "FR12") (pin "1") (pinfunction "1_1") (pintype "passive"))
      (node (ref "IC1") (pin "AG5") (pinfunction "VDD12_LNA_RFE_AG5") (pintype "power_in"))
    )
    (net (code "23") (name "Net-(IC1F-VDD12_RXBUF)") (class "Default")
      (node (ref "C56") (pin "1") (pinfunction "1_1") (pintype "passive"))
      (node (ref "IC1") (pin "AP26") (pinfunction "VDD12_RXBUF_AP26") (pintype "power_in"))
      (node (ref "R29") (pin "1") (pinfunction "1_1") (pintype "passive"))
    )
    (net (code "24") (name "Net-(IC1F-VDD12_TIA_RFE)") (class "Default")
      (node (ref "C61") (pin "2") (pinfunction "2_2") (pintype "passive"))
      (node (ref "FR11") (pin "1") (pinfunction "1_1") (pintype "passive"))
      (node (ref "IC1") (pin "AD6") (pinfunction "VDD12_TIA_RFE_AD6") (pintype "power_in"))
    )
    (net (code "25") (name "Net-(IC1F-VDD12_TXBUF)") (class "Default")
      (node (ref "C48") (pin "1") (pinfunction "1_1") (pintype "passive"))
      (node (ref "IC1") (pin "G5") (pinfunction "VDD12_TXBUF_G5") (pintype "power_in"))
      (node (ref "R28") (pin "1") (pinfunction "1_1") (pintype "passive"))
    )
    (net (code "26") (name "Net-(IC1F-VDD12_VCO_SXR)") (class "Default")
      (node (ref "C57") (pin "1") (pinfunction "1_1") (pintype "passive"))
      (node (ref "FR15") (pin "1") (pinfunction "1_1") (pintype "passive"))
      (node (ref "IC1") (pin "AN23") (pinfunction "VDD12_VCO_SXR_AN23") (pintype "power_in"))
    )
    (net (code "27") (name "Net-(IC1F-VDD14_LNA_RFE)") (class "Default")
      (node (ref "C68") (pin "1") (pinfunction "1_1") (pintype "passive"))
      (node (ref "C69") (pin "1") (pinfunction "1_1") (pintype "passive"))
      (node (ref "C70") (pin "1") (pinfunction "1_1") (pintype "passive"))
      (node (ref "FR24") (pin "1") (pinfunction "1_1") (pintype "passive"))
      (node (ref "IC1") (pin "AD4") (pinfunction "VDD14_RBB_AD4") (pintype "power_in"))
      (node (ref "IC1") (pin "AF2") (pinfunction "VDD14_TIA_RFE_AF2") (pintype "power_in"))
      (node (ref "IC1") (pin "AF6") (pinfunction "VDD14_LNA_RFE_AF6") (pintype "power_in"))
    )
    (net (code "28") (name "Net-(IC1F-VDD14_VCO_CGEN)") (class "Default")
      (node (ref "C66") (pin "1") (pinfunction "1_1") (pintype "passive"))
      (node (ref "C67") (pin "1") (pinfunction "1_1") (pintype "passive"))
      (node (ref "FR25") (pin "1") (pinfunction "1_1") (pintype "passive"))
      (node (ref "IC1") (pin "C21") (pinfunction "VDD14_VCO_CGEN_C21") (pintype "power_in"))
    )
    (net (code "29") (name "Net-(IC1F-VDDO_DIV_SXT)") (class "Default")
      (node (ref "C65") (pin "1") (pinfunction "1_1") (pintype "passive"))
      (node (ref "FR22") (pin "1") (pinfunction "1_1") (pintype "passive"))
      (node (ref "IC1") (pin "K2") (pinfunction "VDDO_DIV_SXT_K2") (pintype "power_in"))
      (node (ref "IC1") (pin "L5") (pinfunction "VDD_DIV_SXT_L5") (pintype "power_in"))
    )
    (net (code "30") (name "Net-(IC1F-VDDO_TLOBUF_TRF)") (class "Default")
      (node (ref "C50") (pin "1") (pinfunction "1_1") (pintype "passive"))
      (node (ref "FR21") (pin "1") (pinfunction "1_1") (pintype "passive"))
      (node (ref "IC1") (pin "D6") (pinfunction "VDDO_TLOBUF_TRF_D6") (pintype "power_in"))
      (node (ref "IC1") (pin "F8") (pinfunction "VDD_TLOBUF_TRF_F8") (pintype "power_in"))
    )
    (net (code "31") (name "Net-(IC1F-VDD_AFE)") (class "Default")
      (node (ref "C55") (pin "1") (pinfunction "1_1") (pintype "passive"))
      (node (ref "FR17") (pin "1") (pinfunction "1_1") (pintype "passive"))
      (node (ref "IC1") (pin "AJ25") (pinfunction "VDD_AFE_AJ25") (pintype "power_in"))
    )
    (net (code "32") (name "Net-(IC1F-VDD_CP_CGEN)") (class "Default")
      (node (ref "C54") (pin "2") (pinfunction "2_2") (pintype "passive"))
      (node (ref "FR18") (pin "1") (pinfunction "1_1") (pintype "passive"))
      (node (ref "IC1") (pin "F20") (pinfunction "VDD_CP_CGEN_F20") (pintype "power_in"))
    )
    (net (code "33") (name "Net-(IC1F-VDD_CP_SXR)") (class "Default")
      (node (ref "C59") (pin "1") (pinfunction "1_1") (pintype "passive"))
      (node (ref "FR13") (pin "1") (pinfunction "1_1") (pintype "passive"))
      (node (ref "IC1") (pin "AL19") (pinfunction "VDD_CP_SXR_AL19") (pintype "power_in"))
    )
    (net (code "34") (name "Net-(IC1F-VDD_CP_SXT)") (class "Default")
      (node (ref "C62") (pin "1") (pinfunction "1_1") (pintype "passive"))
      (node (ref "FR9") (pin "1") (pinfunction "1_1") (pintype "passive"))
      (node (ref "IC1") (pin "J3") (pinfunction "VDD_CP_SXT_J3") (pintype "power_in"))
    )
    (net (code "35") (name "Net-(IC1F-VDD_DIV_CGEN)") (class "Default")
      (node (ref "C52") (pin "1") (pinfunction "1_1") (pintype "passive"))
      (node (ref "C53") (pin "1") (pinfunction "1_1") (pintype "passive"))
      (node (ref "FR19") (pin "1") (pinfunction "1_1") (pintype "passive"))
      (node (ref "IC1") (pin "E19") (pinfunction "VDD_DIV_CGEN_E19") (pintype "power_in"))
    )
    (net (code "36") (name "Net-(IC1F-VDD_DIV_SXR)") (class "Default")
      (node (ref "C58") (pin "1") (pinfunction "1_1") (pintype "passive"))
      (node (ref "FR14") (pin "1") (pinfunction "1_1") (pintype "passive"))
      (node (ref "IC1") (pin "AM20") (pinfunction "VDD_DIV_SXR_AM20") (pintype "power_in"))
    )
    (net (code "37") (name "Net-(IC1F-VDD_MXLOBUF_RFE)") (class "Default")
      (node (ref "C71") (pin "1") (pinfunction "1_1") (pintype "passive"))
      (node (ref "FR23") (pin "1") (pinfunction "1_1") (pintype "passive"))
      (node (ref "IC1") (pin "AN17") (pinfunction "VDD_MXLOBUF_RFE_AN17") (pintype "power_in"))
    )
    (net (code "38") (name "Net-(IC1F-VDD_TBB)") (class "Default")
      (node (ref "C49") (pin "1") (pinfunction "1_1") (pintype "passive"))
      (node (ref "FR10") (pin "1") (pinfunction "1_1") (pintype "passive"))
      (node (ref "IC1") (pin "P4") (pinfunction "VDD_TBB_P4") (pintype "power_in"))
    )
    (net (code "39") (name "Net-(IC1F-VDD_TPAD_TRF)") (class "Default")
      (node (ref "C51") (pin "1") (pinfunction "1_1") (pintype "passive"))
      (node (ref "FR20") (pin "1") (pinfunction "1_1") (pintype "passive"))
      (node (ref "IC1") (pin "B16") (pinfunction "VDD_TPAD_TRF_B16") (pintype "power_in"))
    )
    (net (code "40") (name "VCC1P4_LMS") (class "Default")
      (node (ref "FR22") (pin "2") (pinfunction "2_2") (pintype "passive"))
      (node (ref "FR23") (pin "2") (pinfunction "2_2") (pintype "passive"))
      (node (ref "FR24") (pin "2") (pinfunction "2_2") (pintype "passive"))
      (node (ref "FR25") (pin "2") (pinfunction "2_2") (pintype "passive"))
    )
    (net (code "41") (name "VCC1P8_LMS") (class "Default")
      (node (ref "FR26") (pin "2") (pinfunction "2_2") (pintype "passive"))
      (node (ref "FR27") (pin "1") (pinfunction "1_1") (pintype "passive"))
      (node (ref "FR28") (pin "1") (pinfunction "1_1") (pintype "passive"))
      (node (ref "FR29") (pin "2") (pinfunction "2_2") (pintype "passive"))
      (node (ref "FR30") (pin "2") (pinfunction "2_2") (pintype "passive"))
      (node (ref "FR31") (pin "2") (pinfunction "2_2") (pintype "passive"))
      (node (ref "FR32") (pin "2") (pinfunction "2_2") (pintype "passive"))
      (node (ref "FR33") (pin "2") (pinfunction "2_2") (pintype "passive"))
      (node (ref "R30") (pin "2") (pinfunction "2_2") (pintype "passive"))
      (node (ref "R32") (pin "2") (pinfunction "2_2") (pintype "passive"))
      (node (ref "R33") (pin "1") (pinfunction "1_1") (pintype "passive"))
    )
    (net (code "42") (name "VCC1P25_LMS") (class "Default")
      (node (ref "FR10") (pin "2") (pinfunction "2_2") (pintype "passive"))
      (node (ref "FR11") (pin "2") (pinfunction "2_2") (pintype "passive"))
      (node (ref "FR12") (pin "2") (pinfunction "2_2") (pintype "passive"))
      (node (ref "FR13") (pin "2") (pinfunction "2_2") (pintype "passive"))
      (node (ref "FR14") (pin "2") (pinfunction "2_2") (pintype "passive"))
      (node (ref "FR15") (pin "2") (pinfunction "2_2") (pintype "passive"))
      (node (ref "FR16") (pin "2") (pinfunction "2_2") (pintype "passive"))
      (node (ref "FR17") (pin "2") (pinfunction "2_2") (pintype "passive"))
      (node (ref "FR18") (pin "2") (pinfunction "2_2") (pintype "passive"))
      (node (ref "FR19") (pin "2") (pinfunction "2_2") (pintype "passive"))
      (node (ref "FR20") (pin "2") (pinfunction "2_2") (pintype "passive"))
      (node (ref "FR21") (pin "2") (pinfunction "2_2") (pintype "passive"))
      (node (ref "FR5") (pin "2") (pinfunction "2_2") (pintype "passive"))
      (node (ref "FR6") (pin "2") (pinfunction "2_2") (pintype "passive"))
      (node (ref "FR7") (pin "2") (pinfunction "2_2") (pintype "passive"))
      (node (ref "FR8") (pin "2") (pinfunction "2_2") (pintype "passive"))
      (node (ref "FR9") (pin "2") (pinfunction "2_2") (pintype "passive"))
      (node (ref "R27") (pin "1") (pinfunction "1_1") (pintype "passive"))
    )
    (net (code "43") (name "VDIO_LMS") (class "Default")
      (node (ref "R31") (pin "1") (pinfunction "1_1") (pintype "passive"))
    )
  )
)
